# Power_Input.net
KiCad netlist of a schematic drawn in Altium Designer
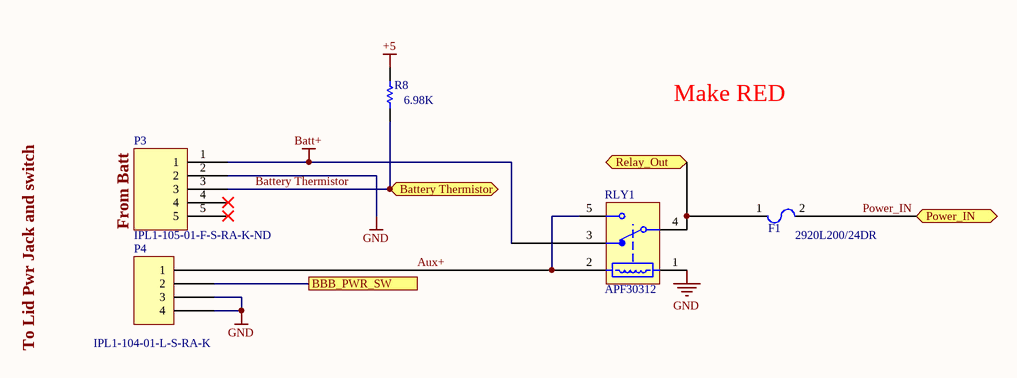
[diagram p0: Power_Input.SchDoc]

(export (version "E")
  (design (tool "Eeschema 10.0.6"))
  (components
    (comp (ref "F1")
      (value "PCT")
      (footprint "CAPC7451X12N")
      (libsource (lib "ZLS_Schematic_lib") (part "PCT"))
    )
    (comp (ref "P3")
      (value "IPL1-105-01-F-S-RA")
      (footprint "IPL1-105-01-F-S-RA")
      (fields (field (name "SUPPLIER PART NUMBER 1") "IPL1-105-01-F-S-RA-K-ND"))
      (libsource (lib "ZLS_Schematic_lib") (part "IPL1-105-01-F-S-RA"))
    )
    (comp (ref "P4")
      (value "IPL1-104-01-L-S-RA-K")
      (footprint "IPL1-104-01-L-S-RA-K")
      (fields
        (field (name "MANUFACTURER") "Samtec Inc.")
        (field (name "MANUFACTURER PART NUMBER") "IPL1-104-01-L-S-RA-K")
      )
      (libsource (lib "ZLS_Schematic_lib") (part "IPL1-104-01-L-S-RA-K"))
    )
    (comp (ref "R8")
      (value "6.98K")
      (footprint "RESC0402(1005)_L")
      (description "RES SMD 6.98K OHM 1% 1/16W 0402")
      (fields
        (field (name "MANUFACTURER") "Yageo")
        (field (name "MANUFACTURER PART NUMBER") "RC0402FR-076K98L")
      )
      (libsource (lib "Altium Content Vault") (part "CMP-1011-00927-1"))
    )
    (comp (ref "RLY1")
      (value "APF30312")
      (footprint "PNSC-PF-5-2800x500x1500_V")
      (fields (field (name "MANUFACTURER") "Panasonic"))
      (libsource (lib "Altium Content Vault") (part "PNSC-APF30312-PF-5-2800x500x1500-5"))
    )
  )
  (nets
    (net (code "1") (name "+5") (class "Default")
      (node (ref "R8") (pin "2") (pinfunction "2_2") (pintype "passive"))
    )
    (net (code "2") (name "/Aux+") (class "Default")
      (node (ref "P4") (pin "1") (pinfunction "1_1") (pintype "passive"))
      (node (ref "RLY1") (pin "2") (pinfunction "2_2") (pintype "passive"))
      (node (ref "RLY1") (pin "5") (pinfunction "NO_5") (pintype "passive"))
    )
    (net (code "3") (name "/BBB_PWR_SW") (class "Default")
      (node (ref "P4") (pin "2") (pinfunction "2_2") (pintype "passive"))
    )
    (net (code "4") (name "/Battery Thermistor") (class "Default")
      (node (ref "P3") (pin "3") (pinfunction "3_3") (pintype "passive"))
      (node (ref "R8") (pin "1") (pinfunction "1_1") (pintype "passive"))
    )
    (net (code "5") (name "/Power_IN") (class "Default")
      (node (ref "F1") (pin "2") (pinfunction "2_2") (pintype "passive"))
    )
    (net (code "6") (name "/Relay_Out") (class "Default")
      (node (ref "F1") (pin "1") (pinfunction "1_1") (pintype "passive"))
      (node (ref "RLY1") (pin "4") (pinfunction "COM_4") (pintype "passive"))
    )
    (net (code "7") (name "Batt+") (class "Default")
      (node (ref "P3") (pin "1") (pinfunction "1_1") (pintype "passive"))
      (node (ref "RLY1") (pin "3") (pinfunction "NC_3") (pintype "passive"))
    )
    (net (code "8") (name "GND") (class "Default")
      (node (ref "P3") (pin "2") (pinfunction "2_2") (pintype "passive"))
      (node (ref "P4") (pin "3") (pinfunction "3_3") (pintype "passive"))
      (node (ref "P4") (pin "4") (pinfunction "4_4") (pintype "passive"))
      (node (ref "RLY1") (pin "1") (pinfunction "1_1") (pintype "passive"))
    )
    (net (code "9") (name "unconnected-(P3-Pad4)") (class "Default")
      (node (ref "P3") (pin "4") (pinfunction "4_4") (pintype "passive+no_connect"))
    )
    (net (code "10") (name "unconnected-(P3-Pad5)") (class "Default")
      (node (ref "P3") (pin "5") (pinfunction "5_5") (pintype "passive+no_connect"))
    )
  )
)
